# NMEA-v8_2-iso.net
KiCad netlist of a schematic drawn in EAGLE
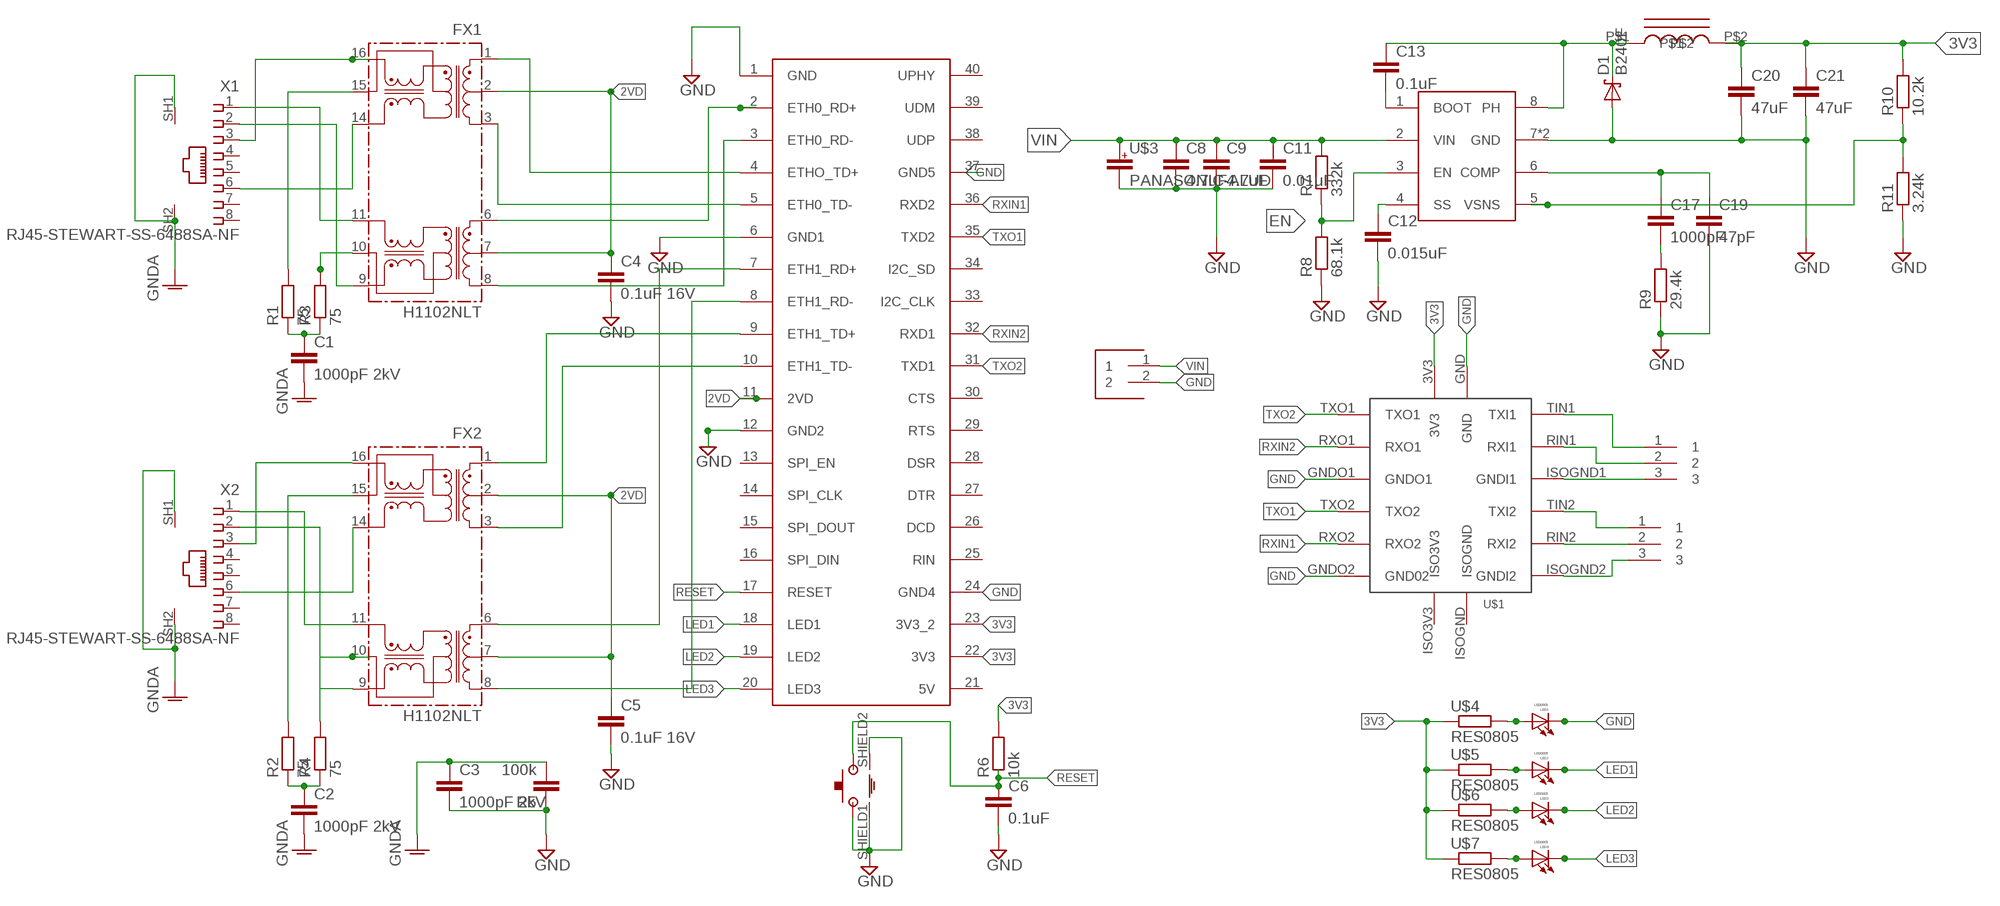
[diagram p0: schematic, sheet 1]

(export (version "E")
  (design (tool "Eeschema 10.0.6"))
  (components
    (comp (ref "C1")
      (value "1000pF 2kV")
      (footprint "eagle-import:1206")
      (libsource (lib "eagle-import") (part "CAP1206"))
    )
    (comp (ref "C2")
      (value "1000pF 2kV")
      (footprint "eagle-import:1206")
      (libsource (lib "eagle-import") (part "CAP1206"))
    )
    (comp (ref "C3")
      (value "1000pF 2kV")
      (footprint "eagle-import:1206")
      (libsource (lib "eagle-import") (part "CAP1206"))
    )
    (comp (ref "C4")
      (value "0.1uF 16V")
      (footprint "eagle-import:0805")
      (libsource (lib "eagle-import") (part "CAP0805"))
    )
    (comp (ref "C5")
      (value "0.1uF 16V")
      (footprint "eagle-import:0805")
      (libsource (lib "eagle-import") (part "CAP0805"))
    )
    (comp (ref "C6")
      (value "0.1uF")
      (footprint "eagle-import:0805")
      (libsource (lib "eagle-import") (part "CAP0805"))
    )
    (comp (ref "C8")
      (value "4.7uF")
      (footprint "eagle-import:1210")
      (libsource (lib "eagle-import") (part "CAP1210"))
    )
    (comp (ref "C9")
      (value "4.7uF")
      (footprint "eagle-import:1210")
      (libsource (lib "eagle-import") (part "CAP1210"))
    )
    (comp (ref "C11")
      (value "0.01uF")
      (footprint "eagle-import:0805")
      (libsource (lib "eagle-import") (part "CAP0805"))
    )
    (comp (ref "C12")
      (value "0.015uF")
      (footprint "eagle-import:0805")
      (libsource (lib "eagle-import") (part "CAP0805"))
    )
    (comp (ref "C13")
      (value "0.1uF")
      (footprint "eagle-import:0805")
      (libsource (lib "eagle-import") (part "CAP0805"))
    )
    (comp (ref "C17")
      (value "1000pF")
      (footprint "eagle-import:0805")
      (libsource (lib "eagle-import") (part "CAP0805"))
    )
    (comp (ref "C19")
      (value "47pF")
      (footprint "eagle-import:0805")
      (libsource (lib "eagle-import") (part "CAP0805"))
    )
    (comp (ref "C20")
      (value "47uF")
      (footprint "eagle-import:1206")
      (libsource (lib "eagle-import") (part "CAP1206"))
    )
    (comp (ref "C21")
      (value "47uF")
      (footprint "eagle-import:1206")
      (libsource (lib "eagle-import") (part "CAP1206"))
    )
    (comp (ref "CARAMBOLA")
      (value "CARAMBOLA")
      (footprint "eagle-import:CARAMBOLA")
      (libsource (lib "eagle-import") (part "CARAMBOLA"))
    )
    (comp (ref "D1")
      (value "B240F")
      (footprint "eagle-import:SMB")
      (libsource (lib "eagle-import") (part "B240F"))
    )
    (comp (ref "DATA1")
      (value "CON-3")
      (footprint "eagle-import:CON-3")
      (libsource (lib "eagle-import") (part "CON-3"))
    )
    (comp (ref "DATA2")
      (value "CON-3")
      (footprint "eagle-import:CON-3")
      (libsource (lib "eagle-import") (part "CON-3"))
    )
    (comp (ref "FX1")
      (value "H1102NLT")
      (footprint "eagle-import:H_HX1XXXNL")
      (libsource (lib "eagle-import") (part "H1102NLT"))
    )
    (comp (ref "FX2")
      (value "H1102NLT")
      (footprint "eagle-import:H_HX1XXXNL")
      (libsource (lib "eagle-import") (part "H1102NLT"))
    )
    (comp (ref "J1")
      (value "CON-5MM-2")
      (footprint "eagle-import:CON--5MM-2")
      (libsource (lib "eagle-import") (part "CON-5MM-2"))
    )
    (comp (ref "L1")
      (value "CLF_TDK_INDUCTORCLF10040")
      (footprint "eagle-import:CLF10040")
      (libsource (lib "eagle-import") (part "CLF_TDK_INDUCTORCLF10040"))
    )
    (comp (ref "LED1")
      (value "LED0805")
      (footprint "eagle-import:L0805")
      (libsource (lib "eagle-import") (part "LED0805"))
    )
    (comp (ref "LED2")
      (value "LED0805")
      (footprint "eagle-import:L0805")
      (libsource (lib "eagle-import") (part "LED0805"))
    )
    (comp (ref "LED3")
      (value "LED0805")
      (footprint "eagle-import:L0805")
      (libsource (lib "eagle-import") (part "LED0805"))
    )
    (comp (ref "LED4")
      (value "LED0805")
      (footprint "eagle-import:L0805")
      (libsource (lib "eagle-import") (part "LED0805"))
    )
    (comp (ref "R1")
      (value "75")
      (footprint "eagle-import:0805")
      (libsource (lib "eagle-import") (part "RES0805"))
    )
    (comp (ref "R2")
      (value "75")
      (footprint "eagle-import:0805")
      (libsource (lib "eagle-import") (part "RES0805"))
    )
    (comp (ref "R3")
      (value "75")
      (footprint "eagle-import:0805")
      (libsource (lib "eagle-import") (part "RES0805"))
    )
    (comp (ref "R4")
      (value "75")
      (footprint "eagle-import:0805")
      (libsource (lib "eagle-import") (part "RES0805"))
    )
    (comp (ref "R5")
      (value "100k")
      (footprint "eagle-import:1206")
      (libsource (lib "eagle-import") (part "CAP1206"))
    )
    (comp (ref "R6")
      (value "10k")
      (footprint "eagle-import:0805")
      (libsource (lib "eagle-import") (part "RES0805"))
    )
    (comp (ref "R7")
      (value "332k")
      (footprint "eagle-import:0805")
      (libsource (lib "eagle-import") (part "RES0805"))
    )
    (comp (ref "R8")
      (value "68.1k")
      (footprint "eagle-import:0805")
      (libsource (lib "eagle-import") (part "RES0805"))
    )
    (comp (ref "R9")
      (value "29.4k")
      (footprint "eagle-import:0805")
      (libsource (lib "eagle-import") (part "RES0805"))
    )
    (comp (ref "R10")
      (value "10.2k")
      (footprint "eagle-import:0805")
      (libsource (lib "eagle-import") (part "RES0805"))
    )
    (comp (ref "R11")
      (value "3.24k")
      (footprint "eagle-import:0805")
      (libsource (lib "eagle-import") (part "RES0805"))
    )
    (comp (ref "U$1")
      (value "ISO-BOARDV1")
      (footprint "eagle-import:ISO-BOARD")
      (libsource (lib "eagle-import") (part "ISO-BOARDV1"))
    )
    (comp (ref "U$2")
      (value "TACTILE-SWITCH-FSMRA1J")
      (footprint "eagle-import:TACTILE-SWITCH-FSMRA1J")
      (libsource (lib "eagle-import") (part "TACTILE-SWITCH-FSMRA1J"))
    )
    (comp (ref "U$3")
      (value "PANASONIC-ALUD")
      (footprint "eagle-import:PANASONIC_D")
      (libsource (lib "eagle-import") (part "PANASONIC-ALUD"))
    )
    (comp (ref "U$4")
      (value "RES0805")
      (footprint "eagle-import:0805")
      (libsource (lib "eagle-import") (part "RES0805"))
    )
    (comp (ref "U$5")
      (value "RES0805")
      (footprint "eagle-import:0805")
      (libsource (lib "eagle-import") (part "RES0805"))
    )
    (comp (ref "U$6")
      (value "RES0805")
      (footprint "eagle-import:0805")
      (libsource (lib "eagle-import") (part "RES0805"))
    )
    (comp (ref "U$7")
      (value "RES0805")
      (footprint "eagle-import:0805")
      (libsource (lib "eagle-import") (part "RES0805"))
    )
    (comp (ref "U8")
      (value "TPS54231")
      (footprint "eagle-import:SOIC-THERMAL")
      (libsource (lib "eagle-import") (part "TPS54231"))
    )
    (comp (ref "X1")
      (value "RJ45-STEWART-SS-6488SA-NF")
      (footprint "eagle-import:RJ45-STEWART-6488")
      (libsource (lib "eagle-import") (part "RJ45-STEWART-SS-6488SA-NF"))
    )
    (comp (ref "X2")
      (value "RJ45-STEWART-SS-6488SA-NF")
      (footprint "eagle-import:RJ45-STEWART-6488")
      (libsource (lib "eagle-import") (part "RJ45-STEWART-SS-6488SA-NF"))
    )
  )
  (nets
    (net (code "1") (name "2VD") (class "Default")
      (node (ref "C4") (pin "1") (pinfunction "1_1") (pintype "passive"))
      (node (ref "C5") (pin "1") (pinfunction "1_1") (pintype "passive"))
      (node (ref "CARAMBOLA") (pin "11") (pinfunction "2VD_11") (pintype "bidirectional"))
      (node (ref "FX1") (pin "2") (pinfunction "2_2") (pintype "passive"))
      (node (ref "FX1") (pin "7") (pinfunction "7_7") (pintype "passive"))
      (node (ref "FX2") (pin "2") (pinfunction "2_2") (pintype "passive"))
      (node (ref "FX2") (pin "7") (pinfunction "7_7") (pintype "passive"))
    )
    (net (code "2") (name "3V3") (class "Default")
      (node (ref "C20") (pin "1") (pinfunction "1_1") (pintype "passive"))
      (node (ref "C21") (pin "1") (pinfunction "1_1") (pintype "passive"))
      (node (ref "CARAMBOLA") (pin "22") (pinfunction "3V3_22") (pintype "bidirectional"))
      (node (ref "CARAMBOLA") (pin "23") (pinfunction "3V3_2_23") (pintype "bidirectional"))
      (node (ref "L1") (pin "P$2") (pinfunction "P$2_P$2") (pintype "bidirectional"))
      (node (ref "R10") (pin "2") (pinfunction "2_2") (pintype "passive"))
      (node (ref "R6") (pin "2") (pinfunction "2_2") (pintype "passive"))
      (node (ref "U$1") (pin "3V3") (pinfunction "3V3_3V3") (pintype "bidirectional"))
      (node (ref "U$4") (pin "1") (pinfunction "1_1") (pintype "passive"))
      (node (ref "U$5") (pin "1") (pinfunction "1_1") (pintype "passive"))
      (node (ref "U$6") (pin "1") (pinfunction "1_1") (pintype "passive"))
      (node (ref "U$7") (pin "1") (pinfunction "1_1") (pintype "passive"))
    )
    (net (code "3") (name "EN") (class "Default")
      (node (ref "R7") (pin "1") (pinfunction "1_1") (pintype "passive"))
      (node (ref "R8") (pin "2") (pinfunction "2_2") (pintype "passive"))
      (node (ref "U8") (pin "3") (pinfunction "EN_3") (pintype "bidirectional"))
    )
    (net (code "4") (name "GND") (class "Default")
      (node (ref "C11") (pin "2") (pinfunction "2_2") (pintype "passive"))
      (node (ref "C12") (pin "2") (pinfunction "2_2") (pintype "passive"))
      (node (ref "C19") (pin "2") (pinfunction "2_2") (pintype "passive"))
      (node (ref "C20") (pin "2") (pinfunction "2_2") (pintype "passive"))
      (node (ref "C21") (pin "2") (pinfunction "2_2") (pintype "passive"))
      (node (ref "C3") (pin "2") (pinfunction "2_2") (pintype "passive"))
      (node (ref "C4") (pin "2") (pinfunction "2_2") (pintype "passive"))
      (node (ref "C5") (pin "2") (pinfunction "2_2") (pintype "passive"))
      (node (ref "C6") (pin "2") (pinfunction "2_2") (pintype "passive"))
      (node (ref "C8") (pin "2") (pinfunction "2_2") (pintype "passive"))
      (node (ref "C9") (pin "2") (pinfunction "2_2") (pintype "passive"))
      (node (ref "CARAMBOLA") (pin "1") (pinfunction "GND_1") (pintype "bidirectional"))
      (node (ref "CARAMBOLA") (pin "12") (pinfunction "GND2_12") (pintype "bidirectional"))
      (node (ref "CARAMBOLA") (pin "24") (pinfunction "GND4_24") (pintype "bidirectional"))
      (node (ref "CARAMBOLA") (pin "37") (pinfunction "GND5_37") (pintype "bidirectional"))
      (node (ref "CARAMBOLA") (pin "6") (pinfunction "GND1_6") (pintype "bidirectional"))
      (node (ref "D1") (pin "A") (pinfunction "A_A") (pintype "passive"))
      (node (ref "J1") (pin "2") (pinfunction "2_2") (pintype "bidirectional"))
      (node (ref "LED1") (pin "C") (pinfunction "C_C") (pintype "passive"))
      (node (ref "R11") (pin "1") (pinfunction "1_1") (pintype "passive"))
      (node (ref "R5") (pin "1") (pinfunction "1_1") (pintype "passive"))
      (node (ref "R8") (pin "1") (pinfunction "1_1") (pintype "passive"))
      (node (ref "R9") (pin "1") (pinfunction "1_1") (pintype "passive"))
      (node (ref "U$1") (pin "GND") (pinfunction "GND_GND") (pintype "bidirectional"))
      (node (ref "U$1") (pin "GNDO1") (pinfunction "GNDO1_GNDO1") (pintype "bidirectional"))
      (node (ref "U$1") (pin "GNDO2") (pinfunction "GND02_GNDO2") (pintype "bidirectional"))
      (node (ref "U$2") (pin "2") (pinfunction "2_2") (pintype "bidirectional"))
      (node (ref "U$2") (pin "SHIELD1") (pinfunction "SHIELD1_SHIELD1") (pintype "bidirectional"))
      (node (ref "U$2") (pin "SHIELD2") (pinfunction "SHIELD2_SHIELD2") (pintype "bidirectional"))
      (node (ref "U$3") (pin "-") (pinfunction "-_-") (pintype "passive"))
      (node (ref "U8") (pin "7") (pinfunction "GND_7") (pintype "bidirectional"))
      (node (ref "U8") (pin "P$1") (pinfunction "GND_P$1") (pintype "bidirectional"))
    )
    (net (code "5") (name "GNDA") (class "Default")
      (node (ref "C1") (pin "2") (pinfunction "2_2") (pintype "passive"))
      (node (ref "C2") (pin "2") (pinfunction "2_2") (pintype "passive"))
      (node (ref "C3") (pin "1") (pinfunction "1_1") (pintype "passive"))
      (node (ref "R5") (pin "2") (pinfunction "2_2") (pintype "passive"))
      (node (ref "X1") (pin "SH1") (pinfunction "SH1_SH1") (pintype "bidirectional"))
      (node (ref "X1") (pin "SH2") (pinfunction "SH2_SH2") (pintype "bidirectional"))
      (node (ref "X2") (pin "SH1") (pinfunction "SH1_SH1") (pintype "bidirectional"))
      (node (ref "X2") (pin "SH2") (pinfunction "SH2_SH2") (pintype "bidirectional"))
    )
    (net (code "6") (name "LED1") (class "Default")
      (node (ref "CARAMBOLA") (pin "18") (pinfunction "LED1_18") (pintype "bidirectional"))
      (node (ref "LED2") (pin "C") (pinfunction "C_C") (pintype "passive"))
    )
    (net (code "7") (name "LED2") (class "Default")
      (node (ref "CARAMBOLA") (pin "19") (pinfunction "LED2_19") (pintype "bidirectional"))
      (node (ref "LED3") (pin "C") (pinfunction "C_C") (pintype "passive"))
    )
    (net (code "8") (name "LED3") (class "Default")
      (node (ref "CARAMBOLA") (pin "20") (pinfunction "LED3_20") (pintype "bidirectional"))
      (node (ref "LED4") (pin "C") (pinfunction "C_C") (pintype "passive"))
    )
    (net (code "9") (name "Net-(C1-Pad1)") (class "Default")
      (node (ref "C1") (pin "1") (pinfunction "1_1") (pintype "passive"))
      (node (ref "R1") (pin "1") (pinfunction "1_1") (pintype "passive"))
      (node (ref "R3") (pin "1") (pinfunction "1_1") (pintype "passive"))
    )
    (net (code "10") (name "Net-(C2-Pad1)") (class "Default")
      (node (ref "C2") (pin "1") (pinfunction "1_1") (pintype "passive"))
      (node (ref "R2") (pin "1") (pinfunction "1_1") (pintype "passive"))
      (node (ref "R4") (pin "1") (pinfunction "1_1") (pintype "passive"))
    )
    (net (code "11") (name "Net-(C17-Pad2)") (class "Default")
      (node (ref "C17") (pin "2") (pinfunction "2_2") (pintype "passive"))
      (node (ref "R9") (pin "2") (pinfunction "2_2") (pintype "passive"))
    )
    (net (code "12") (name "Net-(CARAMBOLA-ETH0_RD+)") (class "Default")
      (node (ref "CARAMBOLA") (pin "2") (pinfunction "ETH0_RD+_2") (pintype "bidirectional"))
      (node (ref "FX1") (pin "6") (pinfunction "6_6") (pintype "passive"))
    )
    (net (code "13") (name "Net-(CARAMBOLA-ETH0_RD-)") (class "Default")
      (node (ref "CARAMBOLA") (pin "3") (pinfunction "ETH0_RD-_3") (pintype "bidirectional"))
      (node (ref "FX1") (pin "8") (pinfunction "8_8") (pintype "passive"))
    )
    (net (code "14") (name "Net-(CARAMBOLA-ETH0_TD-)") (class "Default")
      (node (ref "CARAMBOLA") (pin "5") (pinfunction "ETH0_TD-_5") (pintype "bidirectional"))
      (node (ref "FX1") (pin "3") (pinfunction "3_3") (pintype "passive"))
    )
    (net (code "15") (name "Net-(CARAMBOLA-ETH1_RD+)") (class "Default")
      (node (ref "CARAMBOLA") (pin "7") (pinfunction "ETH1_RD+_7") (pintype "bidirectional"))
      (node (ref "FX2") (pin "6") (pinfunction "6_6") (pintype "passive"))
    )
    (net (code "16") (name "Net-(CARAMBOLA-ETH1_RD-)") (class "Default")
      (node (ref "CARAMBOLA") (pin "8") (pinfunction "ETH1_RD-_8") (pintype "bidirectional"))
      (node (ref "FX2") (pin "8") (pinfunction "8_8") (pintype "passive"))
    )
    (net (code "17") (name "Net-(CARAMBOLA-ETH1_TD+)") (class "Default")
      (node (ref "CARAMBOLA") (pin "9") (pinfunction "ETH1_TD+_9") (pintype "bidirectional"))
      (node (ref "FX2") (pin "1") (pinfunction "1_1") (pintype "passive"))
    )
    (net (code "18") (name "Net-(CARAMBOLA-ETH1_TD-)") (class "Default")
      (node (ref "CARAMBOLA") (pin "10") (pinfunction "ETH1_TD-_10") (pintype "bidirectional"))
      (node (ref "FX2") (pin "3") (pinfunction "3_3") (pintype "passive"))
    )
    (net (code "19") (name "Net-(CARAMBOLA-ETHO_TD+)") (class "Default")
      (node (ref "CARAMBOLA") (pin "4") (pinfunction "ETHO_TD+_4") (pintype "bidirectional"))
      (node (ref "FX1") (pin "1") (pinfunction "1_1") (pintype "passive"))
    )
    (net (code "20") (name "Net-(FX1-Pad9)") (class "Default")
      (node (ref "FX1") (pin "9") (pinfunction "9_9") (pintype "passive"))
      (node (ref "X1") (pin "2") (pinfunction "2_2") (pintype "passive"))
    )
    (net (code "21") (name "Net-(FX1-Pad10)") (class "Default")
      (node (ref "FX1") (pin "10") (pinfunction "10_10") (pintype "passive"))
      (node (ref "R3") (pin "2") (pinfunction "2_2") (pintype "passive"))
    )
    (net (code "22") (name "Net-(FX1-Pad11)") (class "Default")
      (node (ref "FX1") (pin "11") (pinfunction "11_11") (pintype "passive"))
      (node (ref "X1") (pin "1") (pinfunction "1_1") (pintype "passive"))
    )
    (net (code "23") (name "Net-(FX1-Pad14)") (class "Default")
      (node (ref "FX1") (pin "14") (pinfunction "14_14") (pintype "passive"))
      (node (ref "X1") (pin "6") (pinfunction "6_6") (pintype "passive"))
    )
    (net (code "24") (name "Net-(FX1-Pad15)") (class "Default")
      (node (ref "FX1") (pin "15") (pinfunction "15_15") (pintype "passive"))
      (node (ref "R1") (pin "2") (pinfunction "2_2") (pintype "passive"))
    )
    (net (code "25") (name "Net-(FX1-Pad16)") (class "Default")
      (node (ref "FX1") (pin "16") (pinfunction "16_16") (pintype "passive"))
      (node (ref "X1") (pin "3") (pinfunction "3_3") (pintype "passive"))
    )
    (net (code "26") (name "Net-(FX2-Pad9)") (class "Default")
      (node (ref "FX2") (pin "9") (pinfunction "9_9") (pintype "passive"))
      (node (ref "X2") (pin "2") (pinfunction "2_2") (pintype "passive"))
    )
    (net (code "27") (name "Net-(FX2-Pad10)") (class "Default")
      (node (ref "FX2") (pin "10") (pinfunction "10_10") (pintype "passive"))
      (node (ref "R4") (pin "2") (pinfunction "2_2") (pintype "passive"))
    )
    (net (code "28") (name "Net-(FX2-Pad11)") (class "Default")
      (node (ref "FX2") (pin "11") (pinfunction "11_11") (pintype "passive"))
      (node (ref "X2") (pin "1") (pinfunction "1_1") (pintype "passive"))
    )
    (net (code "29") (name "Net-(FX2-Pad14)") (class "Default")
      (node (ref "FX2") (pin "14") (pinfunction "14_14") (pintype "passive"))
      (node (ref "X2") (pin "6") (pinfunction "6_6") (pintype "passive"))
    )
    (net (code "30") (name "Net-(FX2-Pad15)") (class "Default")
      (node (ref "FX2") (pin "15") (pinfunction "15_15") (pintype "passive"))
      (node (ref "R2") (pin "2") (pinfunction "2_2") (pintype "passive"))
    )
    (net (code "31") (name "Net-(FX2-Pad16)") (class "Default")
      (node (ref "FX2") (pin "16") (pinfunction "16_16") (pintype "passive"))
      (node (ref "X2") (pin "3") (pinfunction "3_3") (pintype "passive"))
    )
    (net (code "32") (name "Net-(LED1-PadA)") (class "Default")
      (node (ref "LED1") (pin "A") (pinfunction "A_A") (pintype "passive"))
      (node (ref "U$4") (pin "2") (pinfunction "2_2") (pintype "passive"))
    )
    (net (code "33") (name "Net-(LED2-PadA)") (class "Default")
      (node (ref "LED2") (pin "A") (pinfunction "A_A") (pintype "passive"))
      (node (ref "U$5") (pin "2") (pinfunction "2_2") (pintype "passive"))
    )
    (net (code "34") (name "Net-(LED3-PadA)") (class "Default")
      (node (ref "LED3") (pin "A") (pinfunction "A_A") (pintype "passive"))
      (node (ref "U$6") (pin "2") (pinfunction "2_2") (pintype "passive"))
    )
    (net (code "35") (name "Net-(LED4-PadA)") (class "Default")
      (node (ref "LED4") (pin "A") (pinfunction "A_A") (pintype "passive"))
      (node (ref "U$7") (pin "2") (pinfunction "2_2") (pintype "passive"))
    )
    (net (code "36") (name "Net-(U$1-GNDI1)") (class "Default")
      (node (ref "DATA1") (pin "3") (pinfunction "3_3") (pintype "bidirectional"))
      (node (ref "U$1") (pin "ISOGND1") (pinfunction "GNDI1_ISOGND1") (pintype "bidirectional"))
    )
    (net (code "37") (name "Net-(U$1-GNDI2)") (class "Default")
      (node (ref "DATA2") (pin "3") (pinfunction "3_3") (pintype "bidirectional"))
      (node (ref "U$1") (pin "ISOGND2") (pinfunction "GNDI2_ISOGND2") (pintype "bidirectional"))
    )
    (net (code "38") (name "Net-(U$1-RXI1)") (class "Default")
      (node (ref "DATA1") (pin "2") (pinfunction "2_2") (pintype "bidirectional"))
      (node (ref "U$1") (pin "RIN1") (pinfunction "RXI1_RIN1") (pintype "bidirectional"))
    )
    (net (code "39") (name "Net-(U$1-RXI2)") (class "Default")
      (node (ref "DATA2") (pin "2") (pinfunction "2_2") (pintype "bidirectional"))
      (node (ref "U$1") (pin "RIN2") (pinfunction "RXI2_RIN2") (pintype "bidirectional"))
    )
    (net (code "40") (name "Net-(U$1-TXI1)") (class "Default")
      (node (ref "DATA1") (pin "1") (pinfunction "1_1") (pintype "bidirectional"))
      (node (ref "U$1") (pin "TIN1") (pinfunction "TXI1_TIN1") (pintype "bidirectional"))
    )
    (net (code "41") (name "Net-(U$1-TXI2)") (class "Default")
      (node (ref "DATA2") (pin "1") (pinfunction "1_1") (pintype "bidirectional"))
      (node (ref "U$1") (pin "TIN2") (pinfunction "TXI2_TIN2") (pintype "bidirectional"))
    )
    (net (code "42") (name "Net-(U8-BOOT)") (class "Default")
      (node (ref "C13") (pin "2") (pinfunction "2_2") (pintype "passive"))
      (node (ref "U8") (pin "1") (pinfunction "BOOT_1") (pintype "bidirectional"))
    )
    (net (code "43") (name "Net-(U8-COMP)") (class "Default")
      (node (ref "C17") (pin "1") (pinfunction "1_1") (pintype "passive"))
      (node (ref "C19") (pin "1") (pinfunction "1_1") (pintype "passive"))
      (node (ref "U8") (pin "6") (pinfunction "COMP_6") (pintype "bidirectional"))
    )
    (net (code "44") (name "Net-(U8-PH)") (class "Default")
      (node (ref "C13") (pin "1") (pinfunction "1_1") (pintype "passive"))
      (node (ref "D1") (pin "C") (pinfunction "C_C") (pintype "passive"))
      (node (ref "L1") (pin "P$1") (pinfunction "P$1_P$1") (pintype "bidirectional"))
      (node (ref "U8") (pin "8") (pinfunction "PH_8") (pintype "bidirectional"))
    )
    (net (code "45") (name "Net-(U8-SS)") (class "Default")
      (node (ref "C12") (pin "1") (pinfunction "1_1") (pintype "passive"))
      (node (ref "U8") (pin "4") (pinfunction "SS_4") (pintype "bidirectional"))
    )
    (net (code "46") (name "Net-(U8-VSNS)") (class "Default")
      (node (ref "R10") (pin "1") (pinfunction "1_1") (pintype "passive"))
      (node (ref "R11") (pin "2") (pinfunction "2_2") (pintype "passive"))
      (node (ref "U8") (pin "5") (pinfunction "VSNS_5") (pintype "bidirectional"))
    )
    (net (code "47") (name "RESET") (class "Default")
      (node (ref "C6") (pin "1") (pinfunction "1_1") (pintype "passive"))
      (node (ref "CARAMBOLA") (pin "17") (pinfunction "RESET_17") (pintype "bidirectional"))
      (node (ref "R6") (pin "1") (pinfunction "1_1") (pintype "passive"))
      (node (ref "U$2") (pin "1") (pinfunction "1_1") (pintype "bidirectional"))
    )
    (net (code "48") (name "RXIN1") (class "Default")
      (node (ref "CARAMBOLA") (pin "36") (pinfunction "RXD2_36") (pintype "bidirectional"))
      (node (ref "U$1") (pin "RXO2") (pinfunction "RXO2_RXO2") (pintype "bidirectional"))
    )
    (net (code "49") (name "RXIN2") (class "Default")
      (node (ref "CARAMBOLA") (pin "32") (pinfunction "RXD1_32") (pintype "bidirectional"))
      (node (ref "U$1") (pin "RXO1") (pinfunction "RXO1_RXO1") (pintype "bidirectional"))
    )
    (net (code "50") (name "TXO1") (class "Default")
      (node (ref "CARAMBOLA") (pin "35") (pinfunction "TXD2_35") (pintype "bidirectional"))
      (node (ref "U$1") (pin "TXO2") (pinfunction "TXO2_TXO2") (pintype "bidirectional"))
    )
    (net (code "51") (name "TXO2") (class "Default")
      (node (ref "CARAMBOLA") (pin "31") (pinfunction "TXD1_31") (pintype "bidirectional"))
      (node (ref "U$1") (pin "TXO1") (pinfunction "TXO1_TXO1") (pintype "bidirectional"))
    )
    (net (code "52") (name "VIN") (class "Default")
      (node (ref "C11") (pin "1") (pinfunction "1_1") (pintype "passive"))
      (node (ref "C8") (pin "1") (pinfunction "1_1") (pintype "passive"))
      (node (ref "C9") (pin "1") (pinfunction "1_1") (pintype "passive"))
      (node (ref "J1") (pin "1") (pinfunction "1_1") (pintype "bidirectional"))
      (node (ref "R7") (pin "2") (pinfunction "2_2") (pintype "passive"))
      (node (ref "U$3") (pin "+") (pinfunction "+_+") (pintype "passive"))
      (node (ref "U8") (pin "2") (pinfunction "VIN_2") (pintype "bidirectional"))
    )
    (net (code "53") (name "unconnected-(CARAMBOLA-5V-Pad21)") (class "Default")
      (node (ref "CARAMBOLA") (pin "21") (pinfunction "5V_21") (pintype "bidirectional"))
    )
    (net (code "54") (name "unconnected-(CARAMBOLA-CTS-Pad30)") (class "Default")
      (node (ref "CARAMBOLA") (pin "30") (pinfunction "CTS_30") (pintype "bidirectional"))
    )
    (net (code "55") (name "unconnected-(CARAMBOLA-DCD-Pad26)") (class "Default")
      (node (ref "CARAMBOLA") (pin "26") (pinfunction "DCD_26") (pintype "bidirectional"))
    )
    (net (code "56") (name "unconnected-(CARAMBOLA-DSR-Pad28)") (class "Default")
      (node (ref "CARAMBOLA") (pin "28") (pinfunction "DSR_28") (pintype "bidirectional"))
    )
    (net (code "57") (name "unconnected-(CARAMBOLA-DTR-Pad27)") (class "Default")
      (node (ref "CARAMBOLA") (pin "27") (pinfunction "DTR_27") (pintype "bidirectional"))
    )
    (net (code "58") (name "unconnected-(CARAMBOLA-I2C_CLK-Pad33)") (class "Default")
      (node (ref "CARAMBOLA") (pin "33") (pinfunction "I2C_CLK_33") (pintype "bidirectional"))
    )
    (net (code "59") (name "unconnected-(CARAMBOLA-I2C_SD-Pad34)") (class "Default")
      (node (ref "CARAMBOLA") (pin "34") (pinfunction "I2C_SD_34") (pintype "bidirectional"))
    )
    (net (code "60") (name "unconnected-(CARAMBOLA-RIN-Pad25)") (class "Default")
      (node (ref "CARAMBOLA") (pin "25") (pinfunction "RIN_25") (pintype "bidirectional"))
    )
    (net (code "61") (name "unconnected-(CARAMBOLA-RTS-Pad29)") (class "Default")
      (node (ref "CARAMBOLA") (pin "29") (pinfunction "RTS_29") (pintype "bidirectional"))
    )
    (net (code "62") (name "unconnected-(CARAMBOLA-SPI_CLK-Pad14)") (class "Default")
      (node (ref "CARAMBOLA") (pin "14") (pinfunction "SPI_CLK_14") (pintype "bidirectional"))
    )
    (net (code "63") (name "unconnected-(CARAMBOLA-SPI_DIN-Pad16)") (class "Default")
      (node (ref "CARAMBOLA") (pin "16") (pinfunction "SPI_DIN_16") (pintype "bidirectional"))
    )
    (net (code "64") (name "unconnected-(CARAMBOLA-SPI_DOUT-Pad15)") (class "Default")
      (node (ref "CARAMBOLA") (pin "15") (pinfunction "SPI_DOUT_15") (pintype "bidirectional"))
    )
    (net (code "65") (name "unconnected-(CARAMBOLA-SPI_EN-Pad13)") (class "Default")
      (node (ref "CARAMBOLA") (pin "13") (pinfunction "SPI_EN_13") (pintype "bidirectional"))
    )
    (net (code "66") (name "unconnected-(CARAMBOLA-UDM-Pad39)") (class "Default")
      (node (ref "CARAMBOLA") (pin "39") (pinfunction "UDM_39") (pintype "bidirectional"))
    )
    (net (code "67") (name "unconnected-(CARAMBOLA-UDP-Pad38)") (class "Default")
      (node (ref "CARAMBOLA") (pin "38") (pinfunction "UDP_38") (pintype "bidirectional"))
    )
    (net (code "68") (name "unconnected-(CARAMBOLA-UPHY-Pad40)") (class "Default")
      (node (ref "CARAMBOLA") (pin "40") (pinfunction "UPHY_40") (pintype "bidirectional"))
    )
    (net (code "69") (name "unconnected-(U$1-PadISO3V3)") (class "Default")
      (node (ref "U$1") (pin "ISO3V3") (pinfunction "ISO3V3_ISO3V3") (pintype "bidirectional"))
    )
    (net (code "70") (name "unconnected-(U$1-PadISOGND)") (class "Default")
      (node (ref "U$1") (pin "ISOGND") (pinfunction "ISOGND_ISOGND") (pintype "bidirectional"))
    )
    (net (code "71") (name "unconnected-(X1-Pad4)") (class "Default")
      (node (ref "X1") (pin "4") (pinfunction "4_4") (pintype "passive"))
    )
    (net (code "72") (name "unconnected-(X1-Pad5)") (class "Default")
      (node (ref "X1") (pin "5") (pinfunction "5_5") (pintype "passive"))
    )
    (net (code "73") (name "unconnected-(X1-Pad7)") (class "Default")
      (node (ref "X1") (pin "7") (pinfunction "7_7") (pintype "passive"))
    )
    (net (code "74") (name "unconnected-(X1-Pad8)") (class "Default")
      (node (ref "X1") (pin "8") (pinfunction "8_8") (pintype "passive"))
    )
    (net (code "75") (name "unconnected-(X2-Pad4)") (class "Default")
      (node (ref "X2") (pin "4") (pinfunction "4_4") (pintype "passive"))
    )
    (net (code "76") (name "unconnected-(X2-Pad5)") (class "Default")
      (node (ref "X2") (pin "5") (pinfunction "5_5") (pintype "passive"))
    )
    (net (code "77") (name "unconnected-(X2-Pad7)") (class "Default")
      (node (ref "X2") (pin "7") (pinfunction "7_7") (pintype "passive"))
    )
    (net (code "78") (name "unconnected-(X2-Pad8)") (class "Default")
      (node (ref "X2") (pin "8") (pinfunction "8_8") (pintype "passive"))
    )
  )
)
